# Schematic.net
KiCad netlist of a schematic drawn in Altium Designer
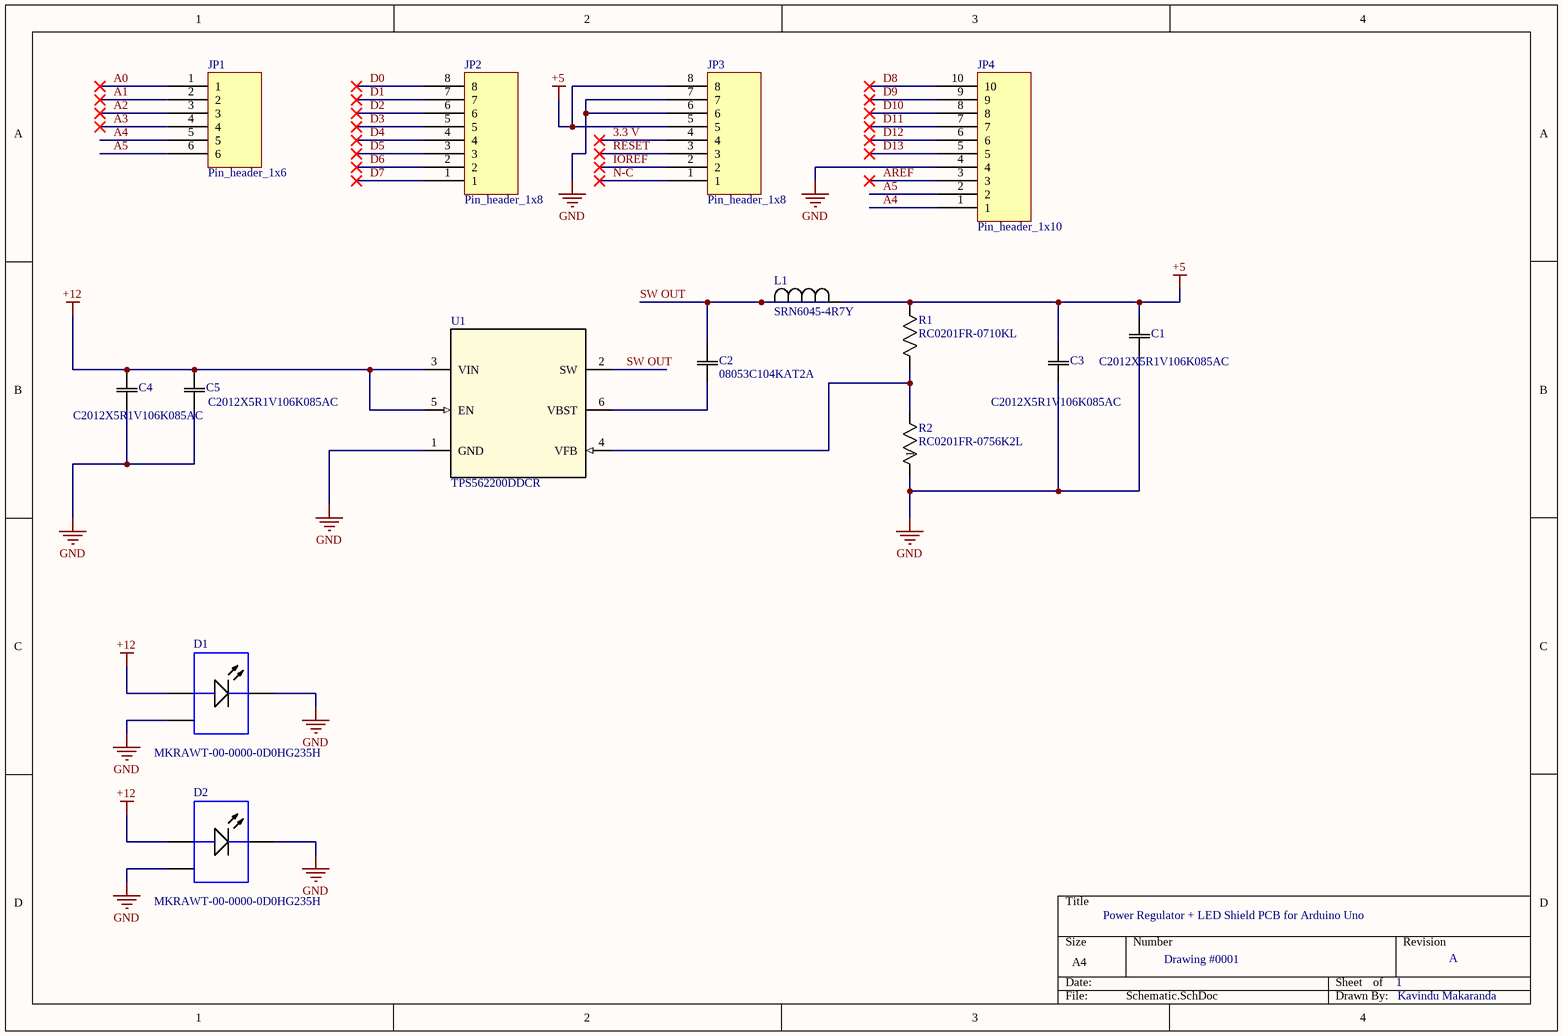
[diagram p0: Schematic.SchDoc]

(export (version "E")
  (design (tool "Eeschema 10.0.6"))
  (components
    (comp (ref "C1")
      (value "C2012X5R1V106K085AC")
      (footprint "6-0805_N")
      (libsource (lib "C2012X5R1V106K085AC") (part "C2012X5R1V106K085AC"))
    )
    (comp (ref "C2")
      (value "08053C104KAT2A")
      (footprint "6-0805_N")
      (libsource (lib "08053C104KAT2A") (part "08053C104KAT2A"))
    )
    (comp (ref "C3")
      (value "C2012X5R1V106K085AC")
      (footprint "6-0805_M")
      (libsource (lib "C2012X5R1V106K085AC") (part "C2012X5R1V106K085AC"))
    )
    (comp (ref "C4")
      (value "C2012X5R1V106K085AC")
      (footprint "6-0805_M")
      (libsource (lib "C2012X5R1V106K085AC") (part "C2012X5R1V106K085AC"))
    )
    (comp (ref "C5")
      (value "C2012X5R1V106K085AC")
      (footprint "6-0805_M")
      (libsource (lib "C2012X5R1V106K085AC") (part "C2012X5R1V106K085AC"))
    )
    (comp (ref "D1")
      (value "MKRAWT-00-0000-0D0HG235H")
      (footprint "CREE-MK-R-2_V")
      (description "LED, White, 12 V, 2-Pin SMD, RoHS, Tape and Reel")
      (libsource (lib "Altium Content Vault") (part "LED_WHITE-3"))
    )
    (comp (ref "D2")
      (value "MKRAWT-00-0000-0D0HG235H")
      (footprint "CREE-MK-R-2_V")
      (description "LED, White, 12 V, 2-Pin SMD, RoHS, Tape and Reel")
      (libsource (lib "Altium Content Vault") (part "LED_WHITE-3"))
    )
    (comp (ref "JP1")
      (value "Pin_header_1x6")
      (footprint "PcbLib1:Pin_header_1x6")
      (libsource (lib "Schlib1") (part "Pin_header_1x6"))
    )
    (comp (ref "JP2")
      (value "Pin_header_1x8")
      (footprint "Pin_header_1x8")
      (libsource (lib "Schlib1") (part "Pin_header_1x8"))
    )
    (comp (ref "JP3")
      (value "Pin_header_1x8")
      (footprint "Pin_header_1x8")
      (libsource (lib "Schlib1") (part "Pin_header_1x8"))
    )
    (comp (ref "JP4")
      (value "Pin_header_1x10")
      (footprint "Pin_header_1x10")
      (libsource (lib "Schlib1") (part "Pin_header_1x10"))
    )
    (comp (ref "L1")
      (value "SRN6045-4R7Y")
      (footprint "SRN6045-4R7Y")
      (description "No Description Available")
      (libsource (lib "SRN6045-4R7Y") (part "SRN6045-4R7Y"))
    )
    (comp (ref "R1")
      (value "RC0201FR-0710KL")
      (footprint "0603")
      (libsource (lib "RC0201FR-0710KL") (part "RC0201FR-0710KL"))
    )
    (comp (ref "R2")
      (value "RC0201FR-0756K2L")
      (footprint "0603")
      (description "No Description Available")
      (libsource (lib "RC0201FR-0756K2L") (part "RC0201FR-0756K2L"))
    )
    (comp (ref "U1")
      (value "TPS562200DDCR")
      (footprint "TPS562200DDCR")
      (description "No Description Available")
      (fields
        (field (name "PARTNUMBER") "TPS562200DDC")
        (field (name "MANUFACTURER") "Texas Instruments")
        (field (name "MODIFIEDDATE") "Not shown in title block")
        (field (name "APPROVEDBY") "Not shown in title block")
        (field (name "CHECKEDBY") "Not shown in title block")
        (field (name "AUTHOR") "Not shown in title block")
        (field (name "ENGINEER") "Not shown in title block")
        (field (name "SYMBOLCREATOR") "a0411947")
        (field (name "PUBLISHER") "Texas Instruments")
      )
      (libsource (lib "TPS562200DDCR") (part "TPS562200DDCR"))
    )
  )
  (nets
    (net (code "1") (name "+5") (class "Default")
      (node (ref "C1") (pin "2") (pinfunction "2_2") (pintype "passive"))
      (node (ref "C3") (pin "2") (pinfunction "2_2") (pintype "passive"))
      (node (ref "JP3") (pin "5") (pinfunction "5_5") (pintype "passive"))
      (node (ref "JP3") (pin "8") (pinfunction "8_8") (pintype "passive"))
      (node (ref "L1") (pin "1") (pinfunction "1_1") (pintype "passive"))
      (node (ref "R1") (pin "2") (pinfunction "2_2") (pintype "passive"))
    )
    (net (code "2") (name "+12") (class "Default")
      (node (ref "C4") (pin "2") (pinfunction "2_2") (pintype "passive"))
      (node (ref "C5") (pin "2") (pinfunction "2_2") (pintype "passive"))
      (node (ref "D1") (pin "1") (pinfunction "A_1") (pintype "passive"))
      (node (ref "D2") (pin "1") (pinfunction "A_1") (pintype "passive"))
      (node (ref "U1") (pin "3") (pinfunction "VIN_3") (pintype "power_in"))
      (node (ref "U1") (pin "5") (pinfunction "EN_5") (pintype "input"))
    )
    (net (code "3") (name "/3.3 V") (class "Default")
      (node (ref "JP3") (pin "4") (pinfunction "4_4") (pintype "passive+no_connect"))
    )
    (net (code "4") (name "/A0") (class "Default")
      (node (ref "JP1") (pin "1") (pinfunction "1_1") (pintype "passive+no_connect"))
    )
    (net (code "5") (name "/A1") (class "Default")
      (node (ref "JP1") (pin "2") (pinfunction "2_2") (pintype "passive+no_connect"))
    )
    (net (code "6") (name "/A2") (class "Default")
      (node (ref "JP1") (pin "3") (pinfunction "3_3") (pintype "passive+no_connect"))
    )
    (net (code "7") (name "/A3") (class "Default")
      (node (ref "JP1") (pin "4") (pinfunction "4_4") (pintype "passive+no_connect"))
    )
    (net (code "8") (name "/A4") (class "Default")
      (node (ref "JP1") (pin "5") (pinfunction "5_5") (pintype "passive"))
      (node (ref "JP4") (pin "1") (pinfunction "1_1") (pintype "passive"))
    )
    (net (code "9") (name "/A5") (class "Default")
      (node (ref "JP1") (pin "6") (pinfunction "6_6") (pintype "passive"))
      (node (ref "JP4") (pin "2") (pinfunction "2_2") (pintype "passive"))
    )
    (net (code "10") (name "/AREF") (class "Default")
      (node (ref "JP4") (pin "3") (pinfunction "3_3") (pintype "passive+no_connect"))
    )
    (net (code "11") (name "/D0") (class "Default")
      (node (ref "JP2") (pin "8") (pinfunction "8_8") (pintype "passive+no_connect"))
    )
    (net (code "12") (name "/D1") (class "Default")
      (node (ref "JP2") (pin "7") (pinfunction "7_7") (pintype "passive+no_connect"))
    )
    (net (code "13") (name "/D2") (class "Default")
      (node (ref "JP2") (pin "6") (pinfunction "6_6") (pintype "passive+no_connect"))
    )
    (net (code "14") (name "/D3") (class "Default")
      (node (ref "JP2") (pin "5") (pinfunction "5_5") (pintype "passive+no_connect"))
    )
    (net (code "15") (name "/D4") (class "Default")
      (node (ref "JP2") (pin "4") (pinfunction "4_4") (pintype "passive+no_connect"))
    )
    (net (code "16") (name "/D5") (class "Default")
      (node (ref "JP2") (pin "3") (pinfunction "3_3") (pintype "passive+no_connect"))
    )
    (net (code "17") (name "/D6") (class "Default")
      (node (ref "JP2") (pin "2") (pinfunction "2_2") (pintype "passive+no_connect"))
    )
    (net (code "18") (name "/D7") (class "Default")
      (node (ref "JP2") (pin "1") (pinfunction "1_1") (pintype "passive+no_connect"))
    )
    (net (code "19") (name "/D8") (class "Default")
      (node (ref "JP4") (pin "10") (pinfunction "10_10") (pintype "passive+no_connect"))
    )
    (net (code "20") (name "/D9") (class "Default")
      (node (ref "JP4") (pin "9") (pinfunction "9_9") (pintype "passive+no_connect"))
    )
    (net (code "21") (name "/D10") (class "Default")
      (node (ref "JP4") (pin "8") (pinfunction "8_8") (pintype "passive+no_connect"))
    )
    (net (code "22") (name "/D11") (class "Default")
      (node (ref "JP4") (pin "7") (pinfunction "7_7") (pintype "passive+no_connect"))
    )
    (net (code "23") (name "/D12") (class "Default")
      (node (ref "JP4") (pin "6") (pinfunction "6_6") (pintype "passive+no_connect"))
    )
    (net (code "24") (name "/D13") (class "Default")
      (node (ref "JP4") (pin "5") (pinfunction "5_5") (pintype "passive+no_connect"))
    )
    (net (code "25") (name "/IOREF") (class "Default")
      (node (ref "JP3") (pin "2") (pinfunction "2_2") (pintype "passive+no_connect"))
    )
    (net (code "26") (name "/N-C") (class "Default")
      (node (ref "JP3") (pin "1") (pinfunction "1_1") (pintype "passive+no_connect"))
    )
    (net (code "27") (name "/RESET") (class "Default")
      (node (ref "JP3") (pin "3") (pinfunction "3_3") (pintype "passive+no_connect"))
    )
    (net (code "28") (name "/SW OUT") (class "Default")
      (node (ref "C2") (pin "2") (pinfunction "2_2") (pintype "passive"))
      (node (ref "L1") (pin "2") (pinfunction "2_2") (pintype "passive"))
      (node (ref "U1") (pin "2") (pinfunction "SW_2") (pintype "power_in"))
    )
    (net (code "29") (name "GND") (class "Default")
      (node (ref "C1") (pin "1") (pinfunction "1_1") (pintype "passive"))
      (node (ref "C3") (pin "1") (pinfunction "1_1") (pintype "passive"))
      (node (ref "C4") (pin "1") (pinfunction "1_1") (pintype "passive"))
      (node (ref "C5") (pin "1") (pinfunction "1_1") (pintype "passive"))
      (node (ref "D1") (pin "2") (pinfunction "K_2") (pintype "passive"))
      (node (ref "D1") (pin "3") (pinfunction "EP_3") (pintype "passive"))
      (node (ref "D2") (pin "2") (pinfunction "K_2") (pintype "passive"))
      (node (ref "D2") (pin "3") (pinfunction "EP_3") (pintype "passive"))
      (node (ref "JP3") (pin "6") (pinfunction "6_6") (pintype "passive"))
      (node (ref "JP3") (pin "7") (pinfunction "7_7") (pintype "passive"))
      (node (ref "JP4") (pin "4") (pinfunction "4_4") (pintype "passive"))
      (node (ref "R2") (pin "1") (pinfunction "1_1") (pintype "passive"))
      (node (ref "U1") (pin "1") (pinfunction "GND_1") (pintype "power_in"))
    )
    (net (code "30") (name "Net-(U1-VBST)") (class "Default")
      (node (ref "C2") (pin "1") (pinfunction "1_1") (pintype "passive"))
      (node (ref "U1") (pin "6") (pinfunction "VBST_6") (pintype "power_in"))
    )
    (net (code "31") (name "Net-(U1-VFB)") (class "Default")
      (node (ref "R1") (pin "1") (pinfunction "1_1") (pintype "passive"))
      (node (ref "R2") (pin "2") (pinfunction "2_2") (pintype "passive"))
      (node (ref "U1") (pin "4") (pinfunction "VFB_4") (pintype "input"))
    )
  )
)
